# Display.net
KiCad netlist of a schematic drawn in Altium Designer
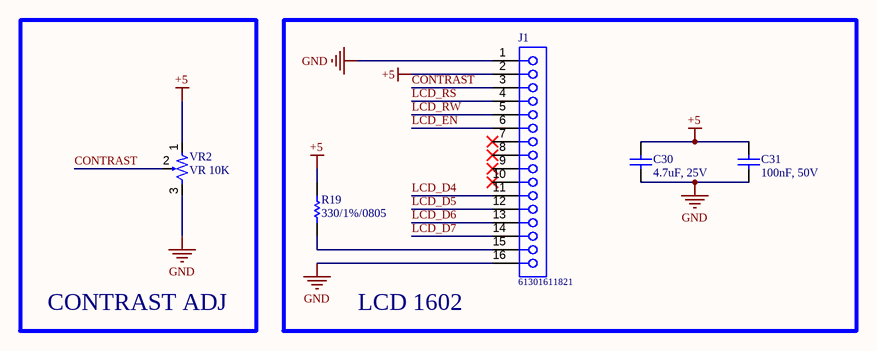
[diagram p0: Display.SchDoc]

(export (version "E")
  (design (tool "Eeschema 10.0.6"))
  (components
    (comp (ref "C30")
      (value "4.7uF, 25V")
      (footprint "WCAP-CSGP_0805_H=1.25mm")
      (description "WCAP-CSGP Multilayer Ceramic Chip Capacitor, General Purpose, size 0805, X5R, 4.7uF, 25V")
      (fields
        (field (name "MANUFACTURER PART NUMBER") "885012107018")
        (field (name "MANUFACTURER") "Wurth Elektronik")
      )
      (libsource (lib "Altium_WCAP-CSGP (rev20a)") (part "885012107018"))
    )
    (comp (ref "C31")
      (value "100nF, 50V")
      (footprint "WCAP-CSGP_0805_H=0.8mm_Wave")
      (description "WCAP-CSGP Multilayer Ceramic Chip Capacitor, General Purpose, size 0805, X7R, 100nF, 50V")
      (fields
        (field (name "MANUFACTURER PART NUMBER") "885012207098")
        (field (name "MANUFACTURER") "Wurth Elektronik")
      )
      (libsource (lib "Altium_WCAP-CSGP (rev20a)") (part "885012207098"))
    )
    (comp (ref "J1")
      (value "61301611821")
      (footprint "61301611821")
      (description "WR-PHD Socket Header, THT, pitch 2.54mm, Single Row, Vertical, 16p")
      (fields (field (name "MANUFACTURER") "Wurth Elektronik"))
      (libsource (lib "Altium_WR-PHD (rev20a)") (part "61301611821"))
    )
    (comp (ref "R19")
      (value "330/1%/0805")
      (footprint "RES-SM-0805")
      (description "Resistor")
      (fields (field (name "Comment") "RESISTOR SMD"))
      (libsource (lib "PIF_Library") (part "RESISTOR SMD"))
    )
    (comp (ref "VR2")
      (value "VR 10K")
      (footprint "VARISTOR 2")
      (description "Var Resistor")
      (fields (field (name "Comment") "10K"))
      (libsource (lib "PIF_Library") (part "Var Resistor"))
    )
  )
  (nets
    (net (code "1") (name "+5") (class "Default")
      (node (ref "C30") (pin "2") (pinfunction "2_2") (pintype "passive"))
      (node (ref "C31") (pin "2") (pinfunction "2_2") (pintype "passive"))
      (node (ref "J1") (pin "2") (pinfunction "2_2") (pintype "passive"))
      (node (ref "R19") (pin "2") (pinfunction "2_2") (pintype "passive"))
      (node (ref "VR2") (pin "1") (pinfunction "1_1") (pintype "passive"))
    )
    (net (code "2") (name "/CONTRAST") (class "Default")
      (node (ref "J1") (pin "3") (pinfunction "3_3") (pintype "passive"))
      (node (ref "VR2") (pin "2") (pinfunction "2_2") (pintype "passive"))
    )
    (net (code "3") (name "/LCD_D4") (class "Default")
      (node (ref "J1") (pin "11") (pinfunction "11_11") (pintype "passive"))
    )
    (net (code "4") (name "/LCD_D5") (class "Default")
      (node (ref "J1") (pin "12") (pinfunction "12_12") (pintype "passive"))
    )
    (net (code "5") (name "/LCD_D6") (class "Default")
      (node (ref "J1") (pin "13") (pinfunction "13_13") (pintype "passive"))
    )
    (net (code "6") (name "/LCD_D7") (class "Default")
      (node (ref "J1") (pin "14") (pinfunction "14_14") (pintype "passive"))
    )
    (net (code "7") (name "/LCD_EN") (class "Default")
      (node (ref "J1") (pin "6") (pinfunction "6_6") (pintype "passive"))
    )
    (net (code "8") (name "/LCD_RS") (class "Default")
      (node (ref "J1") (pin "4") (pinfunction "4_4") (pintype "passive"))
    )
    (net (code "9") (name "/LCD_RW") (class "Default")
      (node (ref "J1") (pin "5") (pinfunction "5_5") (pintype "passive"))
    )
    (net (code "10") (name "GND") (class "Default")
      (node (ref "C30") (pin "1") (pinfunction "1_1") (pintype "passive"))
      (node (ref "C31") (pin "1") (pinfunction "1_1") (pintype "passive"))
      (node (ref "J1") (pin "1") (pinfunction "1_1") (pintype "passive"))
      (node (ref "J1") (pin "16") (pinfunction "16_16") (pintype "passive"))
      (node (ref "VR2") (pin "3") (pinfunction "3_3") (pintype "passive"))
    )
    (net (code "11") (name "Net-(J1-Pad15)") (class "Default")
      (node (ref "J1") (pin "15") (pinfunction "15_15") (pintype "passive"))
      (node (ref "R19") (pin "1") (pinfunction "1_1") (pintype "passive"))
    )
    (net (code "12") (name "unconnected-(J1-Pad7)") (class "Default")
      (node (ref "J1") (pin "7") (pinfunction "7_7") (pintype "passive+no_connect"))
    )
    (net (code "13") (name "unconnected-(J1-Pad8)") (class "Default")
      (node (ref "J1") (pin "8") (pinfunction "8_8") (pintype "passive+no_connect"))
    )
    (net (code "14") (name "unconnected-(J1-Pad9)") (class "Default")
      (node (ref "J1") (pin "9") (pinfunction "9_9") (pintype "passive+no_connect"))
    )
    (net (code "15") (name "unconnected-(J1-Pad10)") (class "Default")
      (node (ref "J1") (pin "10") (pinfunction "10_10") (pintype "passive+no_connect"))
    )
  )
)
